# Photodiode_plate.net
KiCad netlist of a schematic drawn in EasyEDA
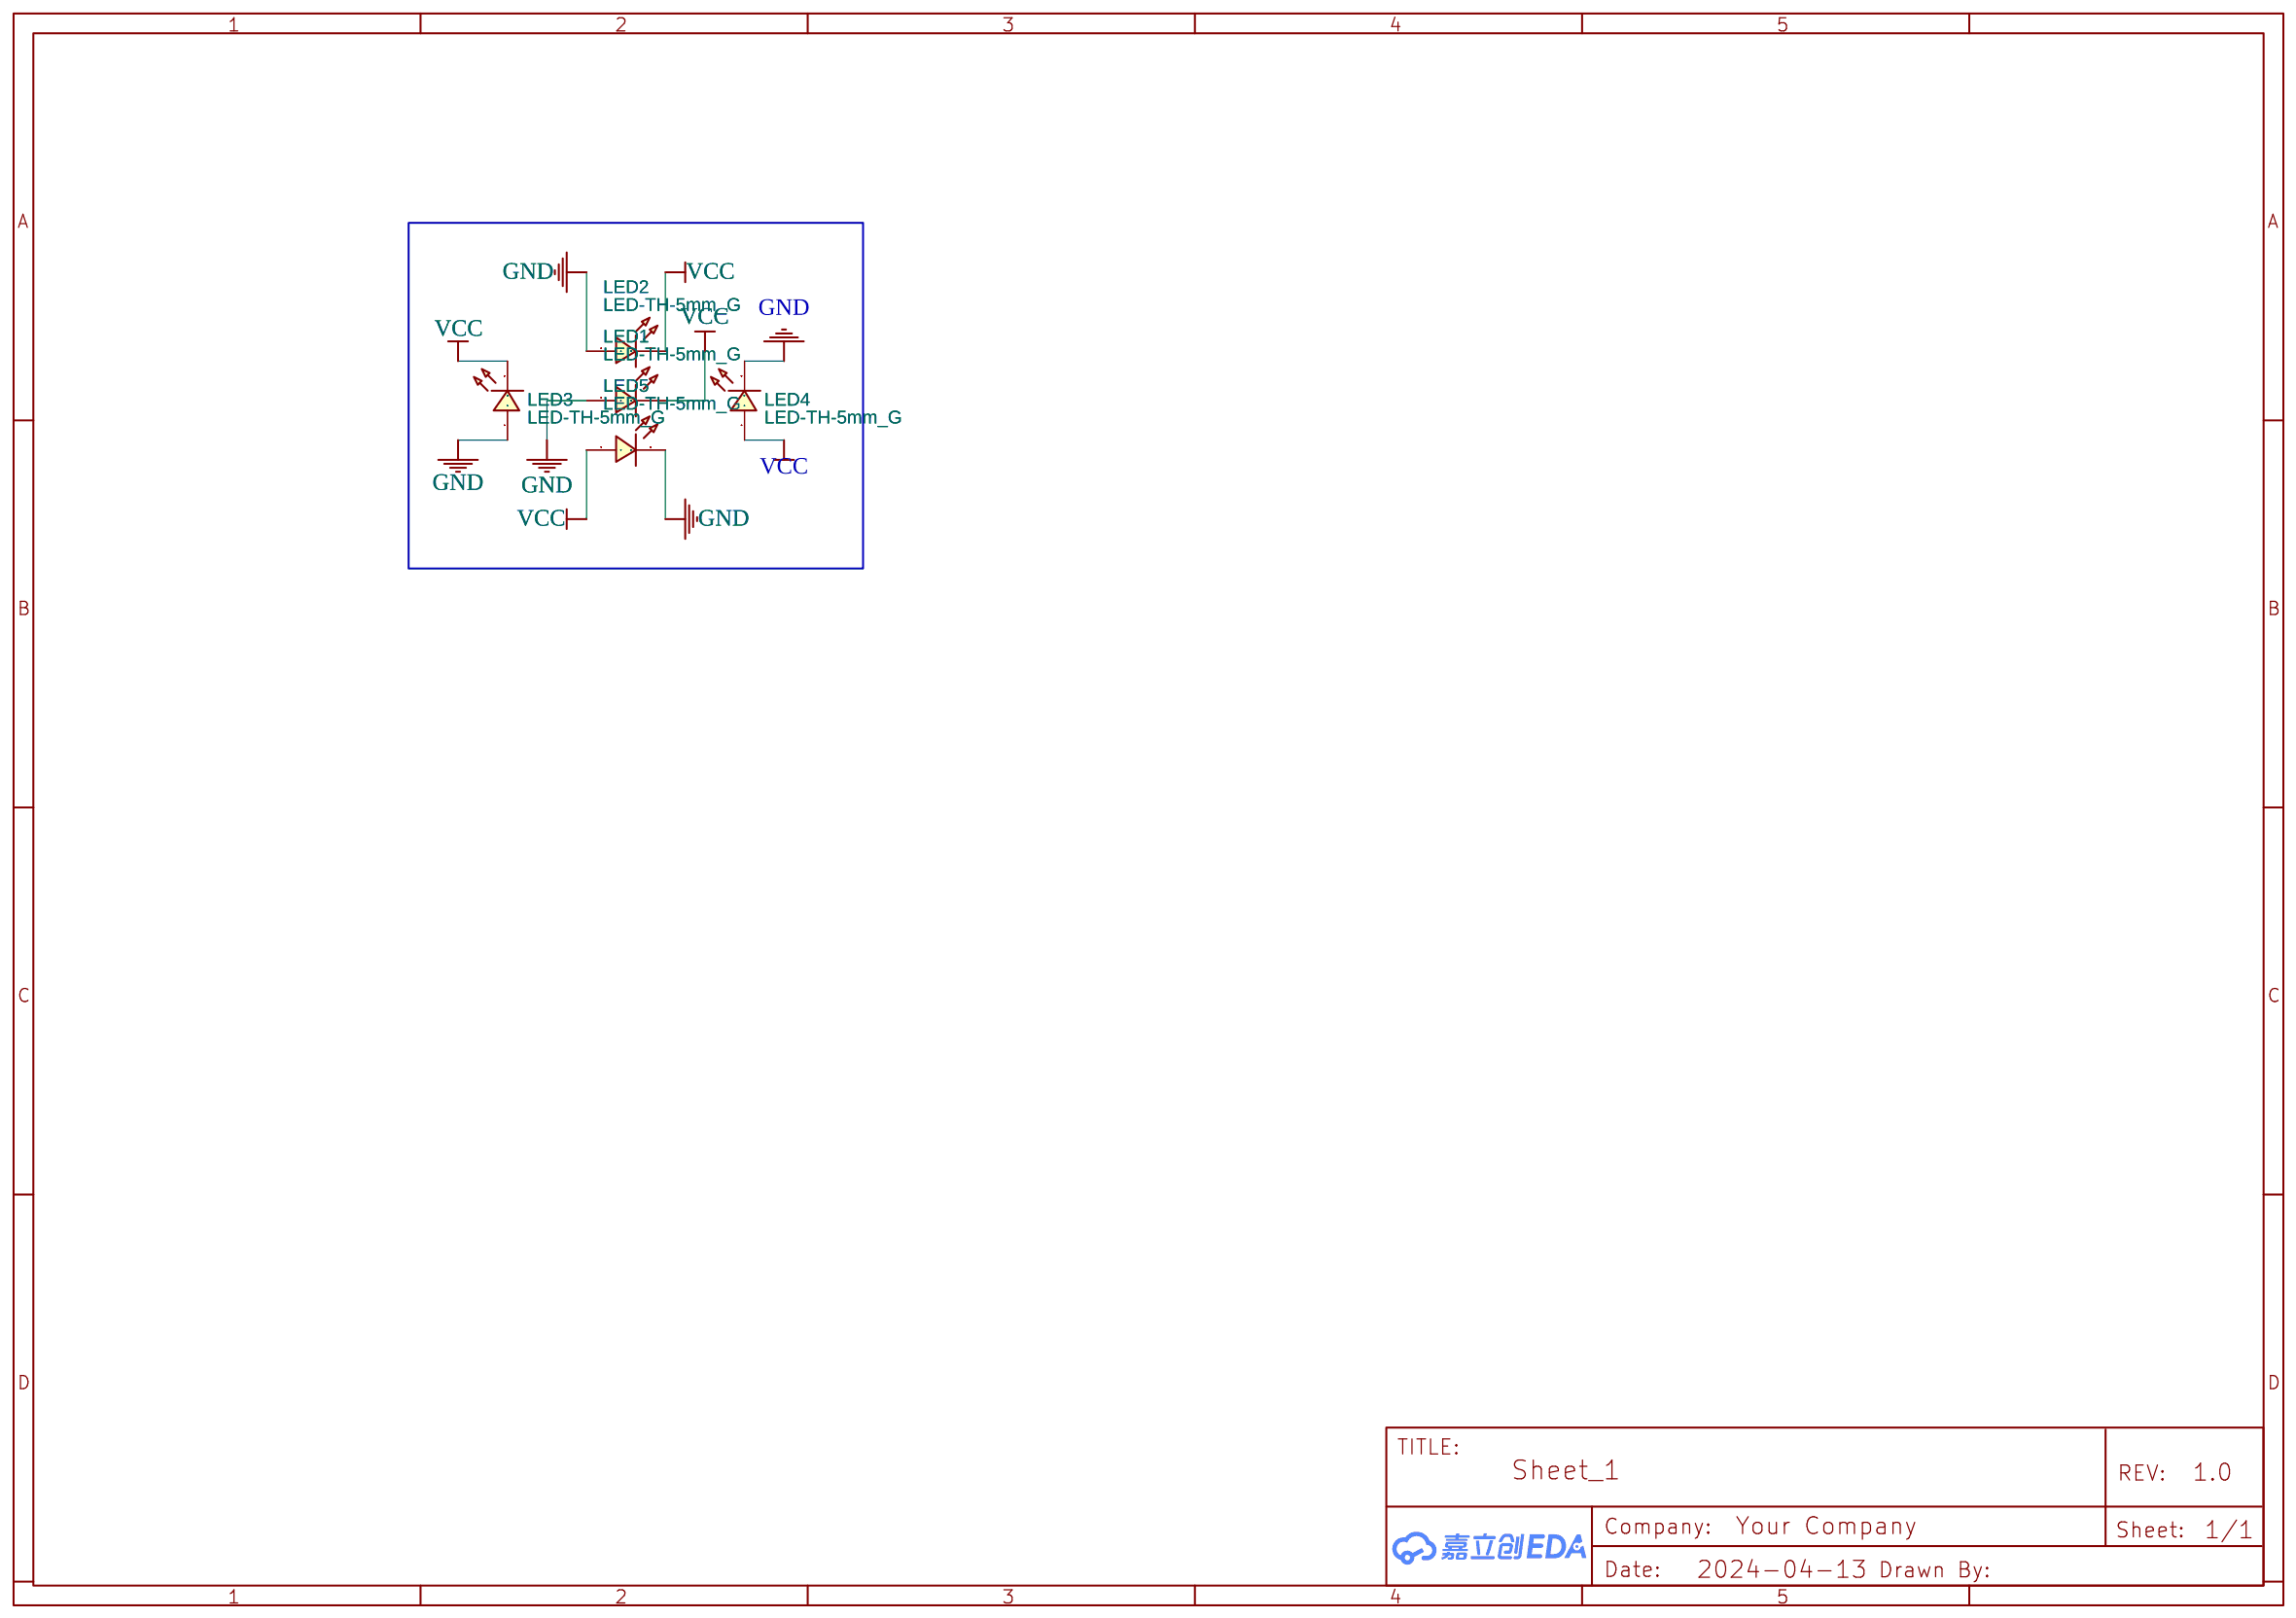
[diagram p0: schematic sheet]

(export (version "E")
  (design (tool "Eeschema 10.0.6"))
  (components
    (comp (ref "LED1")
      (value "LED-TH-5mm_G")
      (fields
        (field (name "BOM_Manufacturer Part") "333-2SYGD/S530-E2")
        (field (name "BOM_Supplier Part") "C88163")
      )
      (libsource (lib "") (part "LED-TH-5mm_G_1"))
    )
    (comp (ref "LED2")
      (value "LED-TH-5mm_G")
      (fields
        (field (name "BOM_Manufacturer Part") "333-2SYGD/S530-E2")
        (field (name "BOM_Supplier Part") "C88163")
      )
      (libsource (lib "") (part "LED-TH-5mm_G_1"))
    )
    (comp (ref "LED3")
      (value "LED-TH-5mm_G")
      (fields
        (field (name "BOM_Manufacturer Part") "333-2SYGD/S530-E2")
        (field (name "BOM_Supplier Part") "C88163")
      )
      (libsource (lib "") (part "LED-TH-5mm_G"))
    )
    (comp (ref "LED4")
      (value "LED-TH-5mm_G")
      (fields
        (field (name "BOM_Manufacturer Part") "333-2SYGD/S530-E2")
        (field (name "BOM_Supplier Part") "C88163")
      )
      (libsource (lib "") (part "LED-TH-5mm_G"))
    )
    (comp (ref "LED5")
      (value "LED-TH-5mm_G")
      (fields
        (field (name "BOM_Manufacturer Part") "333-2SYGD/S530-E2")
        (field (name "BOM_Supplier Part") "C88163")
      )
      (libsource (lib "") (part "LED-TH-5mm_G_1"))
    )
  )
  (nets
    (net (code "1") (name "GND") (class "Default")
      (node (ref "LED1") (pin "1") (pinfunction "1_1") (pintype "unspecified"))
      (node (ref "LED2") (pin "1") (pinfunction "1_1") (pintype "unspecified"))
      (node (ref "LED3") (pin "1") (pinfunction "1_1") (pintype "unspecified"))
      (node (ref "LED4") (pin "2") (pinfunction "2_2") (pintype "unspecified"))
      (node (ref "LED5") (pin "2") (pinfunction "2_2") (pintype "unspecified"))
    )
    (net (code "2") (name "VCC") (class "Default")
      (node (ref "LED1") (pin "2") (pinfunction "2_2") (pintype "unspecified"))
      (node (ref "LED2") (pin "2") (pinfunction "2_2") (pintype "unspecified"))
      (node (ref "LED3") (pin "2") (pinfunction "2_2") (pintype "unspecified"))
      (node (ref "LED4") (pin "1") (pinfunction "1_1") (pintype "unspecified"))
      (node (ref "LED5") (pin "1") (pinfunction "1_1") (pintype "unspecified"))
    )
  )
)
